# power_management.net
KiCad netlist of a schematic drawn in Altium Designer
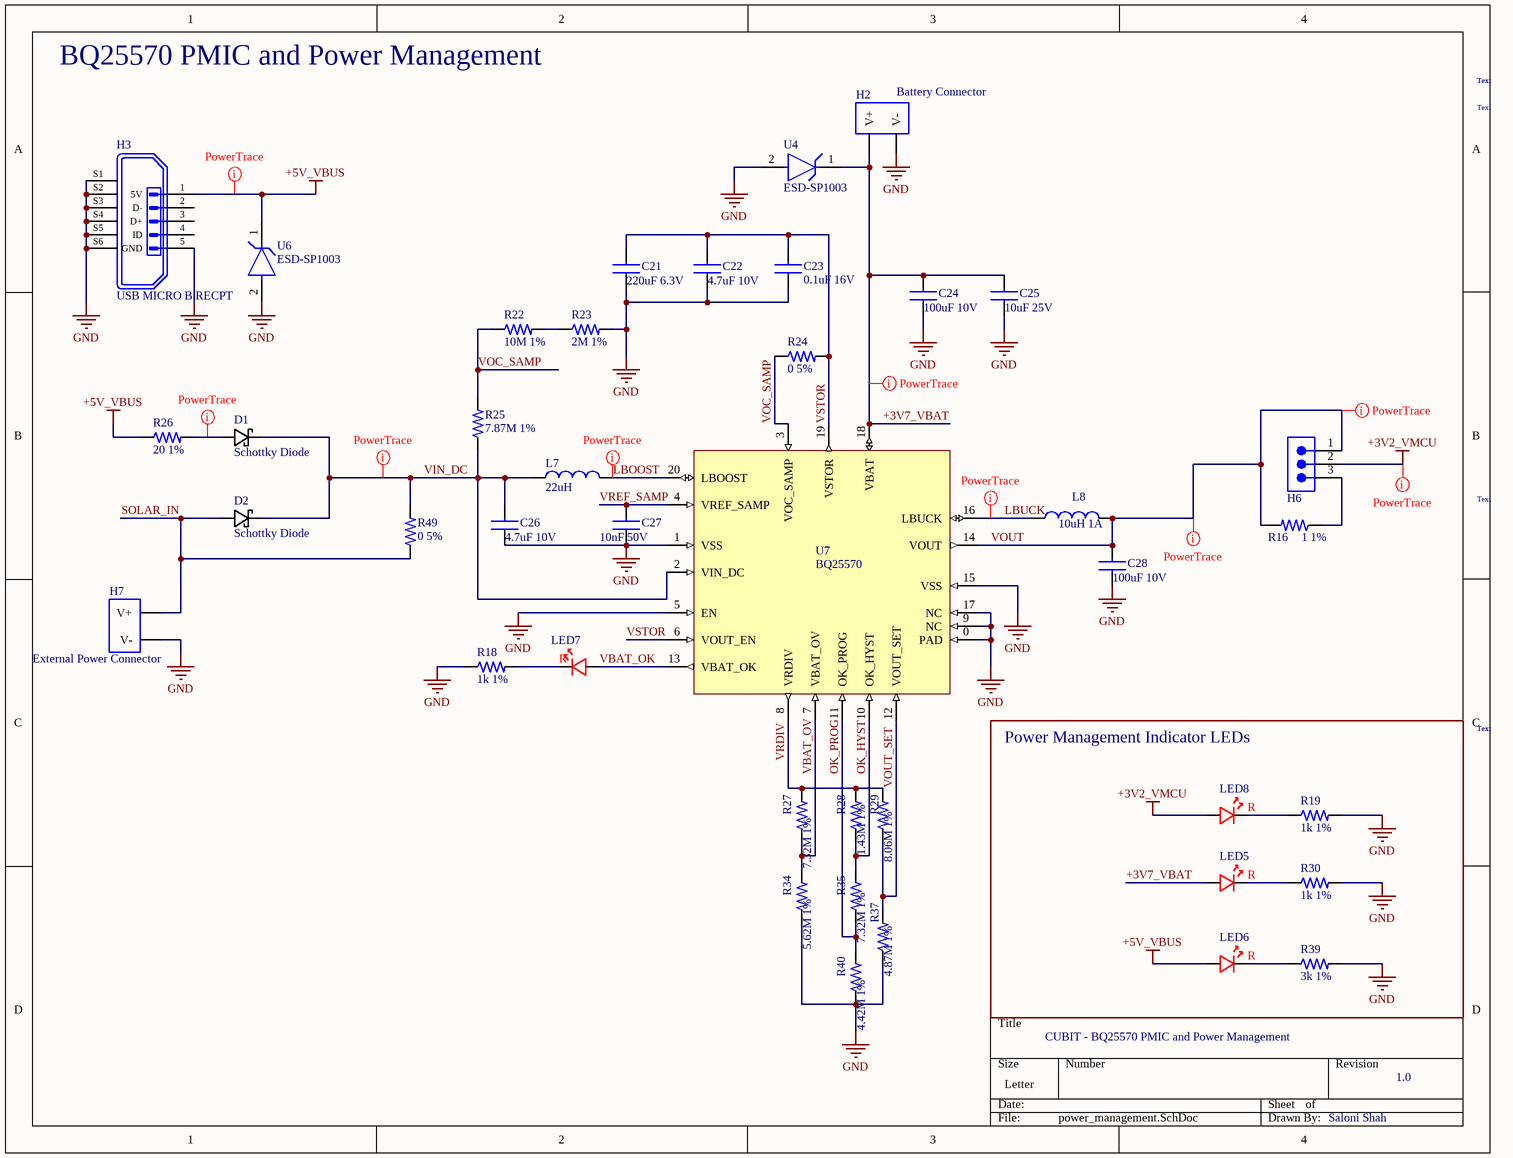
[diagram p0: power_management.SchDoc]

(export (version "E")
  (design (tool "Eeschema 10.0.6"))
  (components
    (comp (ref "C21")
      (value "220uF 6.3V")
      (footprint "Chip_1210_3.2x2.5")
      (description "Cap 220uF 6.3volts X5R 20%")
      (fields
        (field (name "MANUFACTURER") "Murata")
        (field (name "MANUFACTURER PART NUMBER") "GRM32ER60J227ME05L")
      )
      (libsource (lib "LPEDT_proj_lib") (part "GRM32ER60J227ME05L"))
    )
    (comp (ref "C22")
      (value "4.7uF 10V")
      (footprint "LPEDT_proj_lib:CAP_0603_1MM")
      (description "Cap CL10 Series 4.7 uF 10 V ±10 % Tolerance X5R SMT Multilayer Ceramic Capacitor")
      (fields
        (field (name "MANUFACTURER") "Samsung")
        (field (name "MANUFACTURER PART NUMBER") "CL10A475KP8NNNC")
      )
      (libsource (lib "LPEDT_proj_lib") (part "CL10A475KP8NNNC"))
    )
    (comp (ref "C23")
      (value "0.1uF 16V")
      (footprint "LPEDT_proj_lib:CAP_0603_1MM")
      (description "Cap Ceramic 0.1uF 16V X7R 10% SMD 0603 125°C Paper T/R")
      (fields
        (field (name "MANUFACTURER") "KEMET")
        (field (name "MANUFACTURER PART NUMBER") "C0805C104K4RACAUTO")
      )
      (libsource (lib "LPEDT_proj_lib") (part "C0805C104K4RACAUTO"))
    )
    (comp (ref "C24")
      (value "100uF 10V")
      (footprint "Chip_1210_3.2x2.5")
      (description "Cap 100uF ±20% 10V X5R 1210")
      (fields
        (field (name "MANUFACTURER") "Samsung")
        (field (name "MANUFACTURER PART NUMBER") "CL32A107MPVNNNE")
      )
      (libsource (lib "LPEDT_proj_lib") (part "CL32A107MPVNNNE"))
    )
    (comp (ref "C25")
      (value "10uF 25V")
      (footprint "LPEDT_proj_lib:CAP_0805_02X125")
      (description "Cap 0805 25 V 10 uF ±20% Tolerance X5R Monolithic Ceramic Chip Capacitor")
      (fields
        (field (name "MANUFACTURER") "Murata")
        (field (name "MANUFACTURER PART NUMBER") "GRM21BR61E106KA73K")
      )
      (libsource (lib "LPEDT_proj_lib") (part "GRM21BR61E106KA73K"))
    )
    (comp (ref "C26")
      (value "4.7uF 10V")
      (footprint "LPEDT_proj_lib:CAP_0603_1MM")
      (description "Cap CL10 Series 4.7 uF 10 V ±10 % Tolerance X5R SMT Multilayer Ceramic Capacitor")
      (fields
        (field (name "MANUFACTURER") "Samsung")
        (field (name "MANUFACTURER PART NUMBER") "CL10A475KP8NNNC")
      )
      (libsource (lib "LPEDT_proj_lib") (part "CL10A475KP8NNNC"))
    )
    (comp (ref "C27")
      (value "10nF 50V")
      (footprint "LPEDT_proj_lib:CAP_0805_02X125")
      (description "Cap 10nF ±10% 50V X7R 0805")
      (fields
        (field (name "MANUFACTURER") "Samsung")
        (field (name "MANUFACTURER PART NUMBER") "CL21B103KBCNNNC")
      )
      (libsource (lib "LPEDT_proj_lib") (part "CL21B103KBCNNNC"))
    )
    (comp (ref "C28")
      (value "100uF 10V")
      (footprint "Chip_1210_3.2x2.5")
      (description "Cap 100uF ±20% 10V X5R 1210")
      (fields
        (field (name "MANUFACTURER") "Samsung")
        (field (name "MANUFACTURER PART NUMBER") "CL32A107MPVNNNE")
      )
      (libsource (lib "LPEDT_proj_lib") (part "CL32A107MPVNNNE"))
    )
    (comp (ref "D1")
      (value "Schottky Diode")
      (footprint "SCHOTTKY4336X33N")
      (description "LSM115J Series 15 V 1 A Surface Mount Schottky Rectifier - DO-214BA")
      (fields
        (field (name "MANUFACTURER") "Microchip")
        (field (name "MANUFACTURER PART NUMBER") "LSM115JE3/TR13")
      )
      (libsource (lib "LPEDT_proj_lib") (part "LSM115JE3/TR13"))
    )
    (comp (ref "D2")
      (value "Schottky Diode")
      (footprint "SCHOTTKY4336X33N")
      (description "LSM115J Series 15 V 1 A Surface Mount Schottky Rectifier - DO-214BA")
      (fields
        (field (name "MANUFACTURER") "Microchip")
        (field (name "MANUFACTURER PART NUMBER") "LSM115JE3/TR13")
      )
      (libsource (lib "LPEDT_proj_lib") (part "LSM115JE3/TR13"))
    )
    (comp (ref "H2")
      (value "Battery Connector")
      (footprint "BAT_CONN")
      (description "2.00mm Pitch Mi ll System Wire-to-Board Header, Surface Mount, Single Row, Vertical, 2 Circuits")
      (fields (field (name "MANUFACTURER") "Molex") (field (name "MANUFACTURER PART NUMBER") "0554600272"))
      (libsource (lib "LPEDT_proj_lib") (part "0554600272"))
    )
    (comp (ref "H3")
      (value "USB MICRO B RECPT")
      (footprint "MICROUSB_AMPHENOL_10118194-0001LF")
      (description "USB - micro B USB 2.0 Receptacle Connector 5 Position Surface Mount, Right Angle; Through Hole")
      (fields
        (field (name "MANUFACTURER") "Amphenol FCI")
        (field (name "MANUFACTURER PART NUMBER") "10118194-0001LF")
      )
      (libsource (lib "LPEDT_proj_lib") (part "10118194-0001LF"))
    )
    (comp (ref "H6")
      (value "PREC003SAAN-RC")
      (footprint "LPEDT_proj_lib:3_PIN_100mil")
      (description "Connector Header Through Hole 3 position 0.100\" (2.54mm)")
      (fields (field (name "DIGIKEY PART") "S1012EC-03-ND") (field (name "LCSC PART#") "C429954"))
      (libsource (lib "LPEDT_proj_lib") (part "SW_3Pin_100mil_Switch"))
    )
    (comp (ref "H7")
      (value "External Power Connector")
      (footprint "LPEDT_proj_lib:2_PIN_100mil")
      (libsource (lib "LPEDT_proj_lib") (part "ext_pwr_conn"))
    )
    (comp (ref "L7")
      (value "22uH")
      (footprint "2_IND_3x3")
      (description "Inductor Power Shielded Wirewound 22uH 20% 1MHz Ferrite 0.87A 0.496Ohm DCR 1212 T/R")
      (fields
        (field (name "MANUFACTURER") "TDK")
        (field (name "MANUFACTURER PART NUMBER") "VLS3015CX-220M-1")
      )
      (libsource (lib "LPEDT_proj_lib") (part "VLS3015CX-220M-1"))
    )
    (comp (ref "L8")
      (value "10uH 1A")
      (footprint "2_chip_2.5x2")
      (description "Inductor Power Shielded Multi-Layer 10uH 20% 1MHz Metal 0.85A 0.46Ohm DCR 1008 T/R")
      (fields
        (field (name "MANUFACTURER") "Murata")
        (field (name "MANUFACTURER PART NUMBER") "1239AS-H-100M=P2")
      )
      (libsource (lib "LPEDT_proj_lib") (part "1239AS-H-100M=P2"))
    )
    (comp (ref "LED5")
      (value "150060RS75000")
      (footprint "LED_0603_RED_WL-SMCW")
      (description "LED Low-Power Uni-Color Red 630nm 2V 2-Pin Chip 0603(1608Metric) T/R")
      (fields (field (name "MANUFACTURER") "Wurth Electronics"))
      (libsource (lib "LPEDT_proj_lib") (part "150060RS75000"))
    )
    (comp (ref "LED6")
      (value "150060RS75000")
      (footprint "LED_0603_RED_WL-SMCW")
      (description "LED Low-Power Uni-Color Red 630nm 2V 2-Pin Chip 0603(1608Metric) T/R")
      (fields (field (name "MANUFACTURER") "Wurth Electronics"))
      (libsource (lib "LPEDT_proj_lib") (part "150060RS75000"))
    )
    (comp (ref "LED7")
      (value "150060RS75000")
      (footprint "LED_0603_RED_WL-SMCW")
      (description "LED Low-Power Uni-Color Red 630nm 2V 2-Pin Chip 0603(1608Metric) T/R")
      (fields (field (name "MANUFACTURER") "Wurth Electronics"))
      (libsource (lib "LPEDT_proj_lib") (part "150060RS75000"))
    )
    (comp (ref "LED8")
      (value "150060RS75000")
      (footprint "LED_0603_RED_WL-SMCW")
      (description "LED Low-Power Uni-Color Red 630nm 2V 2-Pin Chip 0603(1608Metric) T/R")
      (fields (field (name "MANUFACTURER") "Wurth Electronics"))
      (libsource (lib "LPEDT_proj_lib") (part "150060RS75000"))
    )
    (comp (ref "R16")
      (value "1 1%")
      (footprint "LPEDT_proj_lib:CAP_0603_1MM")
      (description "Res 1 Ohm 1% 1/10W ±200ppm/°C Molded SMD SMD Paper T/R")
      (fields
        (field (name "MANUFACTURER") "Yageo")
        (field (name "MANUFACTURER PART NUMBER") "RC0603FR-101RL")
      )
      (libsource (lib "LPEDT_proj_lib") (part "RC0603FR-101RL"))
    )
    (comp (ref "R18")
      (value "1k 1%")
      (footprint "2_Chip_0603_RMCF")
      (description "Res 1K Ohm 1% 0.1W(1/10W) ±100ppm/C Pad SMD Automotive T/R")
      (fields
        (field (name "MANUFACTURER") "Stackpole Electronics")
        (field (name "MANUFACTURER PART NUMBER") "RMCF0603FT1K00")
      )
      (libsource (lib "LPEDT_proj_lib") (part "RMCF0603FT1K00"))
    )
    (comp (ref "R19")
      (value "1k 1%")
      (footprint "2_Chip_0603_RMCF")
      (description "Res 1K Ohm 1% 0.1W(1/10W) ±100ppm/C Pad SMD Automotive T/R")
      (fields
        (field (name "MANUFACTURER") "Stackpole Electronics")
        (field (name "MANUFACTURER PART NUMBER") "RMCF0603FT1K00")
      )
      (libsource (lib "LPEDT_proj_lib") (part "RMCF0603FT1K00"))
    )
    (comp (ref "R22")
      (value "10M 1%")
      (footprint "2_Chip_0603_RMCF")
      (description "Res 10M Ohm 1% 1/10W ±200ppm/°C Molded SMD SMD Paper T/R")
      (fields
        (field (name "MANUFACTURER") "Stackpole Electronics")
        (field (name "MANUFACTURER PART NUMBER") "RMCF0603FT10M0")
      )
      (libsource (lib "LPEDT_proj_lib") (part "RMCF0603FT10M0"))
    )
    (comp (ref "R23")
      (value "2M 1%")
      (footprint "2_Chip_0603_RMCF")
      (description "RES 2M OHM 1% 1/10W 0603")
      (fields
        (field (name "MANUFACTURER") "Stackpole Electronics")
        (field (name "MANUFACTURER PART NUMBER") "RMCF0603FT2M00")
      )
      (libsource (lib "LPEDT_proj_lib") (part "RMCF0603FT2M00"))
    )
    (comp (ref "R24")
      (value "0 5%")
      (footprint "CAP_0402_1mm")
      (description "Res 0 Ohms ±5% 0.063 W 0402 Thick Film Surface Mount Chip Resistor")
      (fields
        (field (name "MANUFACTURER") "Samsung")
        (field (name "MANUFACTURER PART NUMBER") "RC1005J000CS")
      )
      (libsource (lib "LPEDT_proj_lib") (part "RC1005J000CS"))
    )
    (comp (ref "R25")
      (value "7.87M 1%")
      (footprint "2_Chip_0603_RMCF")
      (description "Res 7.87M Ohm 1% 1/10W ±200ppm/°C Molded SMD SMD Paper T/R")
      (fields
        (field (name "MANUFACTURER") "Stackpole Electronics")
        (field (name "MANUFACTURER PART NUMBER") "RMCF0603FT7M87")
      )
      (libsource (lib "LPEDT_proj_lib") (part "RMCF0603FT7M87"))
    )
    (comp (ref "R26")
      (value "20 1%")
      (footprint "2_Chip_0603_RMCF")
      (description "Res High Voltage 0603 20 Ohm 1/10W 1% SMD")
      (fields (field (name "MANUFACTURER") "Rohm") (field (name "MANUFACTURER PART NUMBER") "KTR03EZPF20R0"))
      (libsource (lib "LPEDT_proj_lib") (part "KTR03EZPF20R0"))
    )
    (comp (ref "R27")
      (value "7.32M 1%")
      (footprint "2_Chip_0603_RMCF")
      (description "Res 7.32M Ohm 1% 1/10W ±200ppm/°C Molded SMD SMD Paper T/R")
      (fields
        (field (name "MANUFACTURER") "Stackpole Electronics")
        (field (name "MANUFACTURER PART NUMBER") "RMCF0603FT7M32")
      )
      (libsource (lib "LPEDT_proj_lib") (part "RMCF0603FT7M32"))
    )
    (comp (ref "R28")
      (value "1.43M 1%")
      (footprint "2_Chip_0603_RMCF")
      (description "Res 1.43M Ohm 1% 1/10W ±200ppm/°C Molded SMD SMD Paper T/R")
      (fields
        (field (name "MANUFACTURER") "Stackpole Electronics")
        (field (name "MANUFACTURER PART NUMBER") "RMCF0603FT1M43")
      )
      (libsource (lib "LPEDT_proj_lib") (part "RMCF0603FT1M43"))
    )
    (comp (ref "R29")
      (value "8.06M 1%")
      (footprint "2_Chip_0603_RMCF")
      (description "Res 8.06M Ohm 1% 1/10W ±200ppm/°C Molded SMD SMD Paper T/R")
      (fields
        (field (name "MANUFACTURER") "Stackpole Electronics")
        (field (name "MANUFACTURER PART NUMBER") "RMCF0603FT8M06")
      )
      (libsource (lib "LPEDT_proj_lib") (part "RMCF0603FT8M06"))
    )
    (comp (ref "R30")
      (value "1k 1%")
      (footprint "2_Chip_0603_RMCF")
      (description "Res 1K Ohm 1% 0.1W(1/10W) ±100ppm/C Pad SMD Automotive T/R")
      (fields
        (field (name "MANUFACTURER") "Stackpole Electronics")
        (field (name "MANUFACTURER PART NUMBER") "RMCF0603FT1K00")
      )
      (libsource (lib "LPEDT_proj_lib") (part "RMCF0603FT1K00"))
    )
    (comp (ref "R34")
      (value "5.62M 1%")
      (footprint "2_Chip_0603_RMCF")
      (description "Res 5.62M Ohm 1% 1/10W ±200ppm/°C Molded SMD SMD Paper T/R")
      (fields
        (field (name "MANUFACTURER") "Stackpole Electronics")
        (field (name "MANUFACTURER PART NUMBER") "RMCF0603FT5M62")
      )
      (libsource (lib "LPEDT_proj_lib") (part "RMCF0603FT5M62"))
    )
    (comp (ref "R35")
      (value "7.32M 1%")
      (footprint "2_Chip_0603_RMCF")
      (description "Res 7.32M Ohm 1% 1/10W ±200ppm/°C Molded SMD SMD Paper T/R")
      (fields
        (field (name "MANUFACTURER") "Stackpole Electronics")
        (field (name "MANUFACTURER PART NUMBER") "RMCF0603FT7M32")
      )
      (libsource (lib "LPEDT_proj_lib") (part "RMCF0603FT7M32"))
    )
    (comp (ref "R37")
      (value "4.87M 1%")
      (footprint "2_Chip_0603_RMCF")
      (description "Res 4.87M Ohm 1% 1/10W ±200ppm/°C Molded SMD SMD Paper T/R")
      (fields
        (field (name "MANUFACTURER") "Stackpole Electronics")
        (field (name "MANUFACTURER PART NUMBER") "RMCF0603FT4M87")
      )
      (libsource (lib "LPEDT_proj_lib") (part "RMCF0603FT4M87"))
    )
    (comp (ref "R39")
      (value "3k 1%")
      (footprint "LPEDT_proj_lib:CAP_0603_1MM")
      (description "Res 3000Ω ± 1.00% 0.1W ± 100ppm/℃ 0603")
      (fields
        (field (name "MANUFACTURER") "Yageo")
        (field (name "MANUFACTURER PART NUMBER") "RC0603FR-073KL")
      )
      (libsource (lib "LPEDT_proj_lib") (part "RC0603FR-073KL"))
    )
    (comp (ref "R40")
      (value "4.42M 1%")
      (footprint "2_Chip_0603_RMCF")
      (description "Res 4.42M Ohm 1% 1/10W ±200ppm/°C Molded SMD SMD Paper T/R")
      (fields
        (field (name "MANUFACTURER") "Stackpole Electronics")
        (field (name "MANUFACTURER PART NUMBER") "RMCF0603FT4M42")
      )
      (libsource (lib "LPEDT_proj_lib") (part "RMCF0603FT4M42"))
    )
    (comp (ref "R49")
      (value "0 5%")
      (footprint "CAP_0402_1mm")
      (description "Res 0 Ohms ±5% 0.063 W 0402 Thick Film Surface Mount Chip Resistor")
      (fields
        (field (name "MANUFACTURER") "Samsung")
        (field (name "MANUFACTURER PART NUMBER") "RC1005J000CS")
      )
      (libsource (lib "LPEDT_proj_lib") (part "RC1005J000CS"))
    )
    (comp (ref "U4")
      (value "ESD-SP1003")
      (footprint "Littelfuse_Inc_SP1003_MFG")
      (description "TVS DIODE 5VWM 12VC SOD723")
      (fields
        (field (name "MANUFACTURER") "Littelfuse")
        (field (name "MANUFACTURER PART NUMBER") "SP1003-01DTG")
      )
      (libsource (lib "LPEDT_proj_lib") (part "SP1003-01DTG"))
    )
    (comp (ref "U6")
      (value "ESD-SP1003")
      (footprint "Littelfuse_Inc_SP1003_MFG")
      (description "TVS DIODE 5VWM 12VC SOD723")
      (fields
        (field (name "MANUFACTURER") "Littelfuse")
        (field (name "MANUFACTURER PART NUMBER") "SP1003-01DTG")
      )
      (libsource (lib "LPEDT_proj_lib") (part "SP1003-01DTG"))
    )
    (comp (ref "U7")
      (value "BQ25570")
      (footprint "21_QFN_35x35")
      (description "Switching Battery Charger Li-Ion/Li-Pol/Supercapacitor 110mA 2.2V to 5.5V 20-Pin VQFN EP T/R")
      (fields
        (field (name "MANUFACTURER") "Texas Instruments")
        (field (name "MANUFACTURER PART NUMBER") "BQ25570RGRT")
      )
      (libsource (lib "LPEDT_proj_lib") (part "BQ25570RGRT"))
    )
  )
  (nets
    (net (code "1") (name "+3V2_VMCU") (class "Default")
      (node (ref "H6") (pin "2") (pinfunction "2_2") (pintype "passive"))
      (node (ref "LED8") (pin "A") (pinfunction "A_A") (pintype "passive"))
    )
    (net (code "2") (name "+5V_VBUS") (class "Default")
      (node (ref "H3") (pin "1") (pinfunction "5V_1") (pintype "power_in"))
      (node (ref "LED6") (pin "A") (pinfunction "A_A") (pintype "passive"))
      (node (ref "R26") (pin "1") (pinfunction "1_1") (pintype "passive"))
      (node (ref "U6") (pin "1") (pinfunction "C_1") (pintype "passive"))
    )
    (net (code "3") (name "/+3V7_VBAT") (class "Default")
      (node (ref "C24") (pin "1") (pinfunction "1_1") (pintype "passive"))
      (node (ref "C25") (pin "1") (pinfunction "1_1") (pintype "passive"))
      (node (ref "H2") (pin "V+") (pinfunction "V+_V+") (pintype "passive"))
      (node (ref "LED5") (pin "A") (pinfunction "A_A") (pintype "passive"))
      (node (ref "U4") (pin "1") (pinfunction "C_1") (pintype "passive"))
      (node (ref "U7") (pin "18") (pinfunction "VBAT_18") (pintype "bidirectional"))
    )
    (net (code "4") (name "/LBOOST") (class "Default")
      (node (ref "L7") (pin "2") (pinfunction "2_2") (pintype "passive"))
      (node (ref "U7") (pin "20") (pinfunction "LBOOST_20") (pintype "bidirectional"))
    )
    (net (code "5") (name "/LBUCK") (class "Default")
      (node (ref "L8") (pin "1") (pinfunction "1_1") (pintype "passive"))
      (node (ref "U7") (pin "16") (pinfunction "LBUCK_16") (pintype "bidirectional"))
    )
    (net (code "6") (name "/OK_HYST") (class "Default")
      (node (ref "R28") (pin "1") (pinfunction "1_1") (pintype "passive"))
      (node (ref "R35") (pin "2") (pinfunction "2_2") (pintype "passive"))
      (node (ref "U7") (pin "10") (pinfunction "OK_HYST_10") (pintype "input"))
    )
    (net (code "7") (name "/OK_PROG") (class "Default")
      (node (ref "R35") (pin "1") (pinfunction "1_1") (pintype "passive"))
      (node (ref "R40") (pin "2") (pinfunction "2_2") (pintype "passive"))
      (node (ref "U7") (pin "11") (pinfunction "OK_PROG_11") (pintype "input"))
    )
    (net (code "8") (name "/SOLAR_IN") (class "Default")
      (node (ref "D2") (pin "A") (pinfunction "A_A") (pintype "passive"))
      (node (ref "H7") (pin "1") (pinfunction "V+_1") (pintype "passive"))
      (node (ref "R49") (pin "1") (pinfunction "1_1") (pintype "passive"))
    )
    (net (code "9") (name "/VBAT_OK") (class "Default")
      (node (ref "LED7") (pin "A") (pinfunction "A_A") (pintype "passive"))
      (node (ref "U7") (pin "13") (pinfunction "VBAT_OK_13") (pintype "output"))
    )
    (net (code "10") (name "/VBAT_OV") (class "Default")
      (node (ref "R27") (pin "1") (pinfunction "1_1") (pintype "passive"))
      (node (ref "R34") (pin "2") (pinfunction "2_2") (pintype "passive"))
      (node (ref "U7") (pin "7") (pinfunction "VBAT_OV_7") (pintype "input"))
    )
    (net (code "11") (name "/VIN_DC") (class "Default")
      (node (ref "C26") (pin "1") (pinfunction "1_1") (pintype "passive"))
      (node (ref "D1") (pin "C") (pinfunction "C_C") (pintype "passive"))
      (node (ref "D2") (pin "C") (pinfunction "C_C") (pintype "passive"))
      (node (ref "L7") (pin "1") (pinfunction "1_1") (pintype "passive"))
      (node (ref "R25") (pin "1") (pinfunction "1_1") (pintype "passive"))
      (node (ref "R49") (pin "2") (pinfunction "2_2") (pintype "passive"))
      (node (ref "U7") (pin "2") (pinfunction "VIN_DC_2") (pintype "input"))
    )
    (net (code "12") (name "/VOC_SAMP") (class "Default")
      (node (ref "R22") (pin "1") (pinfunction "1_1") (pintype "passive"))
      (node (ref "R24") (pin "1") (pinfunction "1_1") (pintype "passive"))
      (node (ref "R25") (pin "2") (pinfunction "2_2") (pintype "passive"))
      (node (ref "U7") (pin "3") (pinfunction "VOC_SAMP_3") (pintype "input"))
    )
    (net (code "13") (name "/VOUT") (class "Default")
      (node (ref "C28") (pin "1") (pinfunction "1_1") (pintype "passive"))
      (node (ref "H6") (pin "1") (pinfunction "1_1") (pintype "passive"))
      (node (ref "L8") (pin "2") (pinfunction "2_2") (pintype "passive"))
      (node (ref "R16") (pin "2") (pinfunction "2_2") (pintype "passive"))
      (node (ref "U7") (pin "14") (pinfunction "VOUT_14") (pintype "output"))
    )
    (net (code "14") (name "/VOUT_SET") (class "Default")
      (node (ref "R29") (pin "1") (pinfunction "1_1") (pintype "passive"))
      (node (ref "R37") (pin "2") (pinfunction "2_2") (pintype "passive"))
      (node (ref "U7") (pin "12") (pinfunction "VOUT_SET_12") (pintype "input"))
    )
    (net (code "15") (name "/VRDIV") (class "Default")
      (node (ref "R27") (pin "2") (pinfunction "2_2") (pintype "passive"))
      (node (ref "R28") (pin "2") (pinfunction "2_2") (pintype "passive"))
      (node (ref "R29") (pin "2") (pinfunction "2_2") (pintype "passive"))
      (node (ref "U7") (pin "8") (pinfunction "VRDIV_8") (pintype "output"))
    )
    (net (code "16") (name "/VREF_SAMP") (class "Default")
      (node (ref "C27") (pin "1") (pinfunction "1_1") (pintype "passive"))
      (node (ref "U7") (pin "4") (pinfunction "VREF_SAMP_4") (pintype "input"))
    )
    (net (code "17") (name "/VSTOR") (class "Default")
      (node (ref "C21") (pin "1") (pinfunction "1_1") (pintype "passive"))
      (node (ref "C22") (pin "1") (pinfunction "1_1") (pintype "passive"))
      (node (ref "C23") (pin "1") (pinfunction "1_1") (pintype "passive"))
      (node (ref "R24") (pin "2") (pinfunction "2_2") (pintype "passive"))
      (node (ref "U7") (pin "19") (pinfunction "VSTOR_19") (pintype "output"))
      (node (ref "U7") (pin "6") (pinfunction "VOUT_EN_6") (pintype "input"))
    )
    (net (code "18") (name "GND") (class "Default")
      (node (ref "C21") (pin "2") (pinfunction "2_2") (pintype "passive"))
      (node (ref "C22") (pin "2") (pinfunction "2_2") (pintype "passive"))
      (node (ref "C23") (pin "2") (pinfunction "2_2") (pintype "passive"))
      (node (ref "C24") (pin "2") (pinfunction "2_2") (pintype "passive"))
      (node (ref "C25") (pin "2") (pinfunction "2_2") (pintype "passive"))
      (node (ref "C26") (pin "2") (pinfunction "2_2") (pintype "passive"))
      (node (ref "C27") (pin "2") (pinfunction "2_2") (pintype "passive"))
      (node (ref "C28") (pin "2") (pinfunction "2_2") (pintype "passive"))
      (node (ref "H2") (pin "V-") (pinfunction "V-_V-") (pintype "passive"))
      (node (ref "H3") (pin "5") (pinfunction "GND_5") (pintype "passive"))
      (node (ref "H3") (pin "S1") (pinfunction "S1_S1") (pintype "passive"))
      (node (ref "H3") (pin "S2") (pinfunction "S2_S2") (pintype "passive"))
      (node (ref "H3") (pin "S3") (pinfunction "S3_S3") (pintype "passive"))
      (node (ref "H3") (pin "S4") (pinfunction "S4_S4") (pintype "passive"))
      (node (ref "H3") (pin "S5") (pinfunction "S5_S5") (pintype "passive"))
      (node (ref "H3") (pin "S6") (pinfunction "S6_S6") (pintype "passive"))
      (node (ref "H7") (pin "2") (pinfunction "V-_2") (pintype "passive"))
      (node (ref "R18") (pin "1") (pinfunction "1_1") (pintype "passive"))
      (node (ref "R19") (pin "2") (pinfunction "2_2") (pintype "passive"))
      (node (ref "R23") (pin "2") (pinfunction "2_2") (pintype "passive"))
      (node (ref "R30") (pin "2") (pinfunction "2_2") (pintype "passive"))
      (node (ref "R34") (pin "1") (pinfunction "1_1") (pintype "passive"))
      (node (ref "R37") (pin "1") (pinfunction "1_1") (pintype "passive"))
      (node (ref "R39") (pin "2") (pinfunction "2_2") (pintype "passive"))
      (node (ref "R40") (pin "1") (pinfunction "1_1") (pintype "passive"))
      (node (ref "U4") (pin "2") (pinfunction "A_2") (pintype "passive"))
      (node (ref "U6") (pin "2") (pinfunction "A_2") (pintype "passive"))
      (node (ref "U7") (pin "0") (pinfunction "PAD_0") (pintype "input"))
      (node (ref "U7") (pin "1") (pinfunction "VSS_1") (pintype "input"))
      (node (ref "U7") (pin "15") (pinfunction "VSS_15") (pintype "input"))
      (node (ref "U7") (pin "17") (pinfunction "NC_17") (pintype "input"))
      (node (ref "U7") (pin "5") (pinfunction "EN_5") (pintype "input"))
      (node (ref "U7") (pin "9") (pinfunction "NC_9") (pintype "input"))
    )
    (net (code "19") (name "Net-(D1-PadA)") (class "Default")
      (node (ref "D1") (pin "A") (pinfunction "A_A") (pintype "passive"))
      (node (ref "R26") (pin "2") (pinfunction "2_2") (pintype "passive"))
    )
    (net (code "20") (name "Net-(H6-Pad3)") (class "Default")
      (node (ref "H6") (pin "3") (pinfunction "3_3") (pintype "passive"))
      (node (ref "R16") (pin "1") (pinfunction "1_1") (pintype "passive"))
    )
    (net (code "21") (name "Net-(LED5-PadC)") (class "Default")
      (node (ref "LED5") (pin "C") (pinfunction "C_C") (pintype "passive"))
      (node (ref "R30") (pin "1") (pinfunction "1_1") (pintype "passive"))
    )
    (net (code "22") (name "Net-(LED6-PadC)") (class "Default")
      (node (ref "LED6") (pin "C") (pinfunction "C_C") (pintype "passive"))
      (node (ref "R39") (pin "1") (pinfunction "1_1") (pintype "passive"))
    )
    (net (code "23") (name "Net-(LED7-PadC)") (class "Default")
      (node (ref "LED7") (pin "C") (pinfunction "C_C") (pintype "passive"))
      (node (ref "R18") (pin "2") (pinfunction "2_2") (pintype "passive"))
    )
    (net (code "24") (name "Net-(LED8-PadC)") (class "Default")
      (node (ref "LED8") (pin "C") (pinfunction "C_C") (pintype "passive"))
      (node (ref "R19") (pin "1") (pinfunction "1_1") (pintype "passive"))
    )
    (net (code "25") (name "Net-(R22-Pad2)") (class "Default")
      (node (ref "R22") (pin "2") (pinfunction "2_2") (pintype "passive"))
      (node (ref "R23") (pin "1") (pinfunction "1_1") (pintype "passive"))
    )
    (net (code "26") (name "unconnected-(H3-D+-Pad3)") (class "Default")
      (node (ref "H3") (pin "3") (pinfunction "D+_3") (pintype "passive"))
    )
    (net (code "27") (name "unconnected-(H3-D--Pad2)") (class "Default")
      (node (ref "H3") (pin "2") (pinfunction "D-_2") (pintype "passive"))
    )
    (net (code "28") (name "unconnected-(H3-ID-Pad4)") (class "Default")
      (node (ref "H3") (pin "4") (pinfunction "ID_4") (pintype "passive"))
    )
  )
)
